# delay.net
KiCad netlist of a schematic drawn in EAGLE
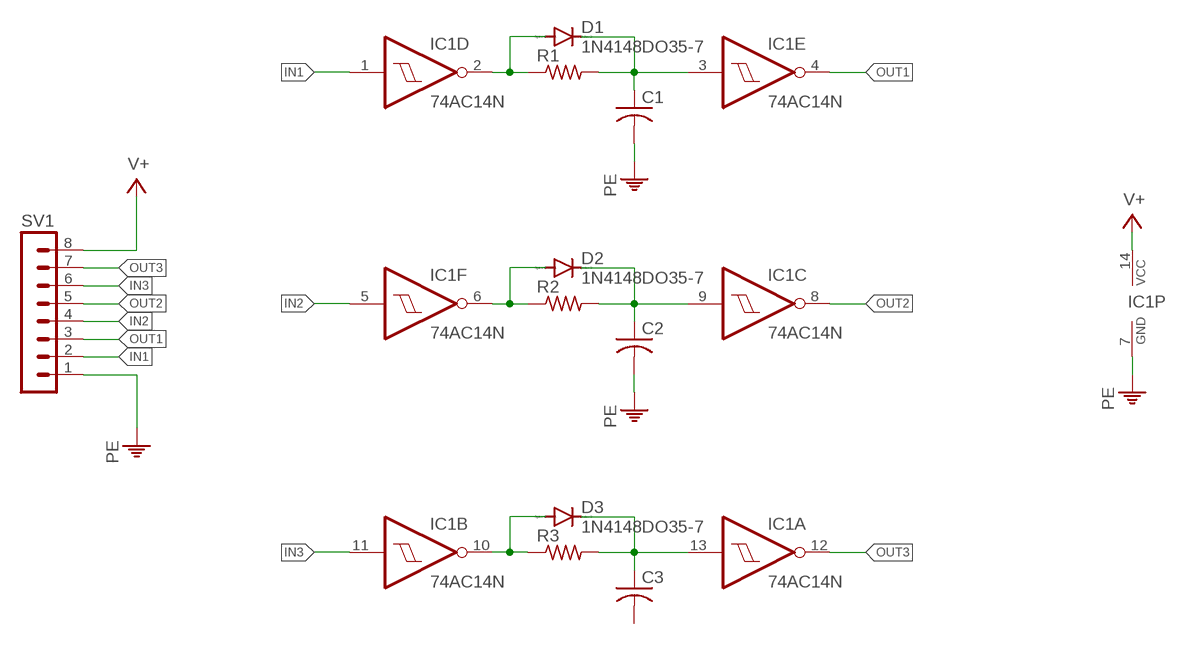
[diagram p0: schematic, sheet 1]

(export (version "E")
  (design (tool "Eeschema 10.0.6"))
  (components
    (comp (ref "C1")
      (value "C-US025-025X050")
      (footprint "eagle-import:C025-025X050")
      (libsource (lib "eagle-import") (part "C-US025-025X050"))
    )
    (comp (ref "C2")
      (value "C-US025-025X050")
      (footprint "eagle-import:C025-025X050")
      (libsource (lib "eagle-import") (part "C-US025-025X050"))
    )
    (comp (ref "C3")
      (value "C-US025-025X050")
      (footprint "eagle-import:C025-025X050")
      (libsource (lib "eagle-import") (part "C-US025-025X050"))
    )
    (comp (ref "D1")
      (value "1N4148DO35-7")
      (footprint "eagle-import:DO35-7")
      (libsource (lib "eagle-import") (part "1N4148DO35-7"))
    )
    (comp (ref "D2")
      (value "1N4148DO35-7")
      (footprint "eagle-import:DO35-7")
      (libsource (lib "eagle-import") (part "1N4148DO35-7"))
    )
    (comp (ref "D3")
      (value "1N4148DO35-7")
      (footprint "eagle-import:DO35-7")
      (libsource (lib "eagle-import") (part "1N4148DO35-7"))
    )
    (comp (ref "IC1")
      (value "74AC14N")
      (footprint "eagle-import:DIL14")
      (libsource (lib "eagle-import") (part "7414NAC"))
    )
    (comp (ref "R1")
      (value "R-US_0204/7")
      (footprint "eagle-import:0204_7")
      (libsource (lib "eagle-import") (part "R-US_0204/7"))
    )
    (comp (ref "R2")
      (value "R-US_0204/7")
      (footprint "eagle-import:0204_7")
      (libsource (lib "eagle-import") (part "R-US_0204/7"))
    )
    (comp (ref "R3")
      (value "R-US_0204/7")
      (footprint "eagle-import:0204_7")
      (libsource (lib "eagle-import") (part "R-US_0204/7"))
    )
    (comp (ref "SV1")
      (value "MA08-1")
      (footprint "eagle-import:MA08-1")
      (libsource (lib "eagle-import") (part "MA08-1"))
    )
  )
  (nets
    (net (code "1") (name "IN1") (class "Default")
      (node (ref "IC1") (pin "1") (pinfunction "I_1") (pintype "input"))
      (node (ref "SV1") (pin "2") (pinfunction "2_2") (pintype "passive"))
    )
    (net (code "2") (name "IN2") (class "Default")
      (node (ref "IC1") (pin "5") (pinfunction "I_5") (pintype "input"))
      (node (ref "SV1") (pin "4") (pinfunction "4_4") (pintype "passive"))
    )
    (net (code "3") (name "IN3") (class "Default")
      (node (ref "IC1") (pin "11") (pinfunction "I_11") (pintype "input"))
      (node (ref "SV1") (pin "6") (pinfunction "6_6") (pintype "passive"))
    )
    (net (code "4") (name "Net-(IC1A-I)") (class "Default")
      (node (ref "C3") (pin "1") (pinfunction "1_1") (pintype "passive"))
      (node (ref "D3") (pin "C") (pinfunction "C_C") (pintype "passive"))
      (node (ref "IC1") (pin "13") (pinfunction "I_13") (pintype "input"))
      (node (ref "R3") (pin "2") (pinfunction "2_2") (pintype "passive"))
    )
    (net (code "5") (name "Net-(IC1B-O)") (class "Default")
      (node (ref "D3") (pin "A") (pinfunction "A_A") (pintype "passive"))
      (node (ref "IC1") (pin "10") (pinfunction "O_10") (pintype "output"))
      (node (ref "R3") (pin "1") (pinfunction "1_1") (pintype "passive"))
    )
    (net (code "6") (name "Net-(IC1C-I)") (class "Default")
      (node (ref "C2") (pin "1") (pinfunction "1_1") (pintype "passive"))
      (node (ref "D2") (pin "C") (pinfunction "C_C") (pintype "passive"))
      (node (ref "IC1") (pin "9") (pinfunction "I_9") (pintype "input"))
      (node (ref "R2") (pin "2") (pinfunction "2_2") (pintype "passive"))
    )
    (net (code "7") (name "Net-(IC1D-O)") (class "Default")
      (node (ref "D1") (pin "A") (pinfunction "A_A") (pintype "passive"))
      (node (ref "IC1") (pin "2") (pinfunction "O_2") (pintype "output"))
      (node (ref "R1") (pin "1") (pinfunction "1_1") (pintype "passive"))
    )
    (net (code "8") (name "Net-(IC1E-I)") (class "Default")
      (node (ref "C1") (pin "1") (pinfunction "1_1") (pintype "passive"))
      (node (ref "D1") (pin "C") (pinfunction "C_C") (pintype "passive"))
      (node (ref "IC1") (pin "3") (pinfunction "I_3") (pintype "input"))
      (node (ref "R1") (pin "2") (pinfunction "2_2") (pintype "passive"))
    )
    (net (code "9") (name "Net-(IC1F-O)") (class "Default")
      (node (ref "D2") (pin "A") (pinfunction "A_A") (pintype "passive"))
      (node (ref "IC1") (pin "6") (pinfunction "O_6") (pintype "output"))
      (node (ref "R2") (pin "1") (pinfunction "1_1") (pintype "passive"))
    )
    (net (code "10") (name "OUT1") (class "Default")
      (node (ref "IC1") (pin "4") (pinfunction "O_4") (pintype "output"))
      (node (ref "SV1") (pin "3") (pinfunction "3_3") (pintype "passive"))
    )
    (net (code "11") (name "OUT2") (class "Default")
      (node (ref "IC1") (pin "8") (pinfunction "O_8") (pintype "output"))
      (node (ref "SV1") (pin "5") (pinfunction "5_5") (pintype "passive"))
    )
    (net (code "12") (name "OUT3") (class "Default")
      (node (ref "IC1") (pin "12") (pinfunction "O_12") (pintype "output"))
      (node (ref "SV1") (pin "7") (pinfunction "7_7") (pintype "passive"))
    )
    (net (code "13") (name "PE") (class "Default")
      (node (ref "C1") (pin "2") (pinfunction "2_2") (pintype "passive"))
      (node (ref "C2") (pin "2") (pinfunction "2_2") (pintype "passive"))
      (node (ref "IC1") (pin "7") (pinfunction "GND_7") (pintype "power_in"))
      (node (ref "SV1") (pin "1") (pinfunction "1_1") (pintype "passive"))
    )
    (net (code "14") (name "V+") (class "Default")
      (node (ref "IC1") (pin "14") (pinfunction "VCC_14") (pintype "power_in"))
      (node (ref "SV1") (pin "8") (pinfunction "8_8") (pintype "passive"))
    )
    (net (code "15") (name "unconnected-(C3-Pad2)") (class "Default")
      (node (ref "C3") (pin "2") (pinfunction "2_2") (pintype "passive"))
    )
  )
)
